# brain-test.net
KiCad netlist of a schematic drawn in EAGLE
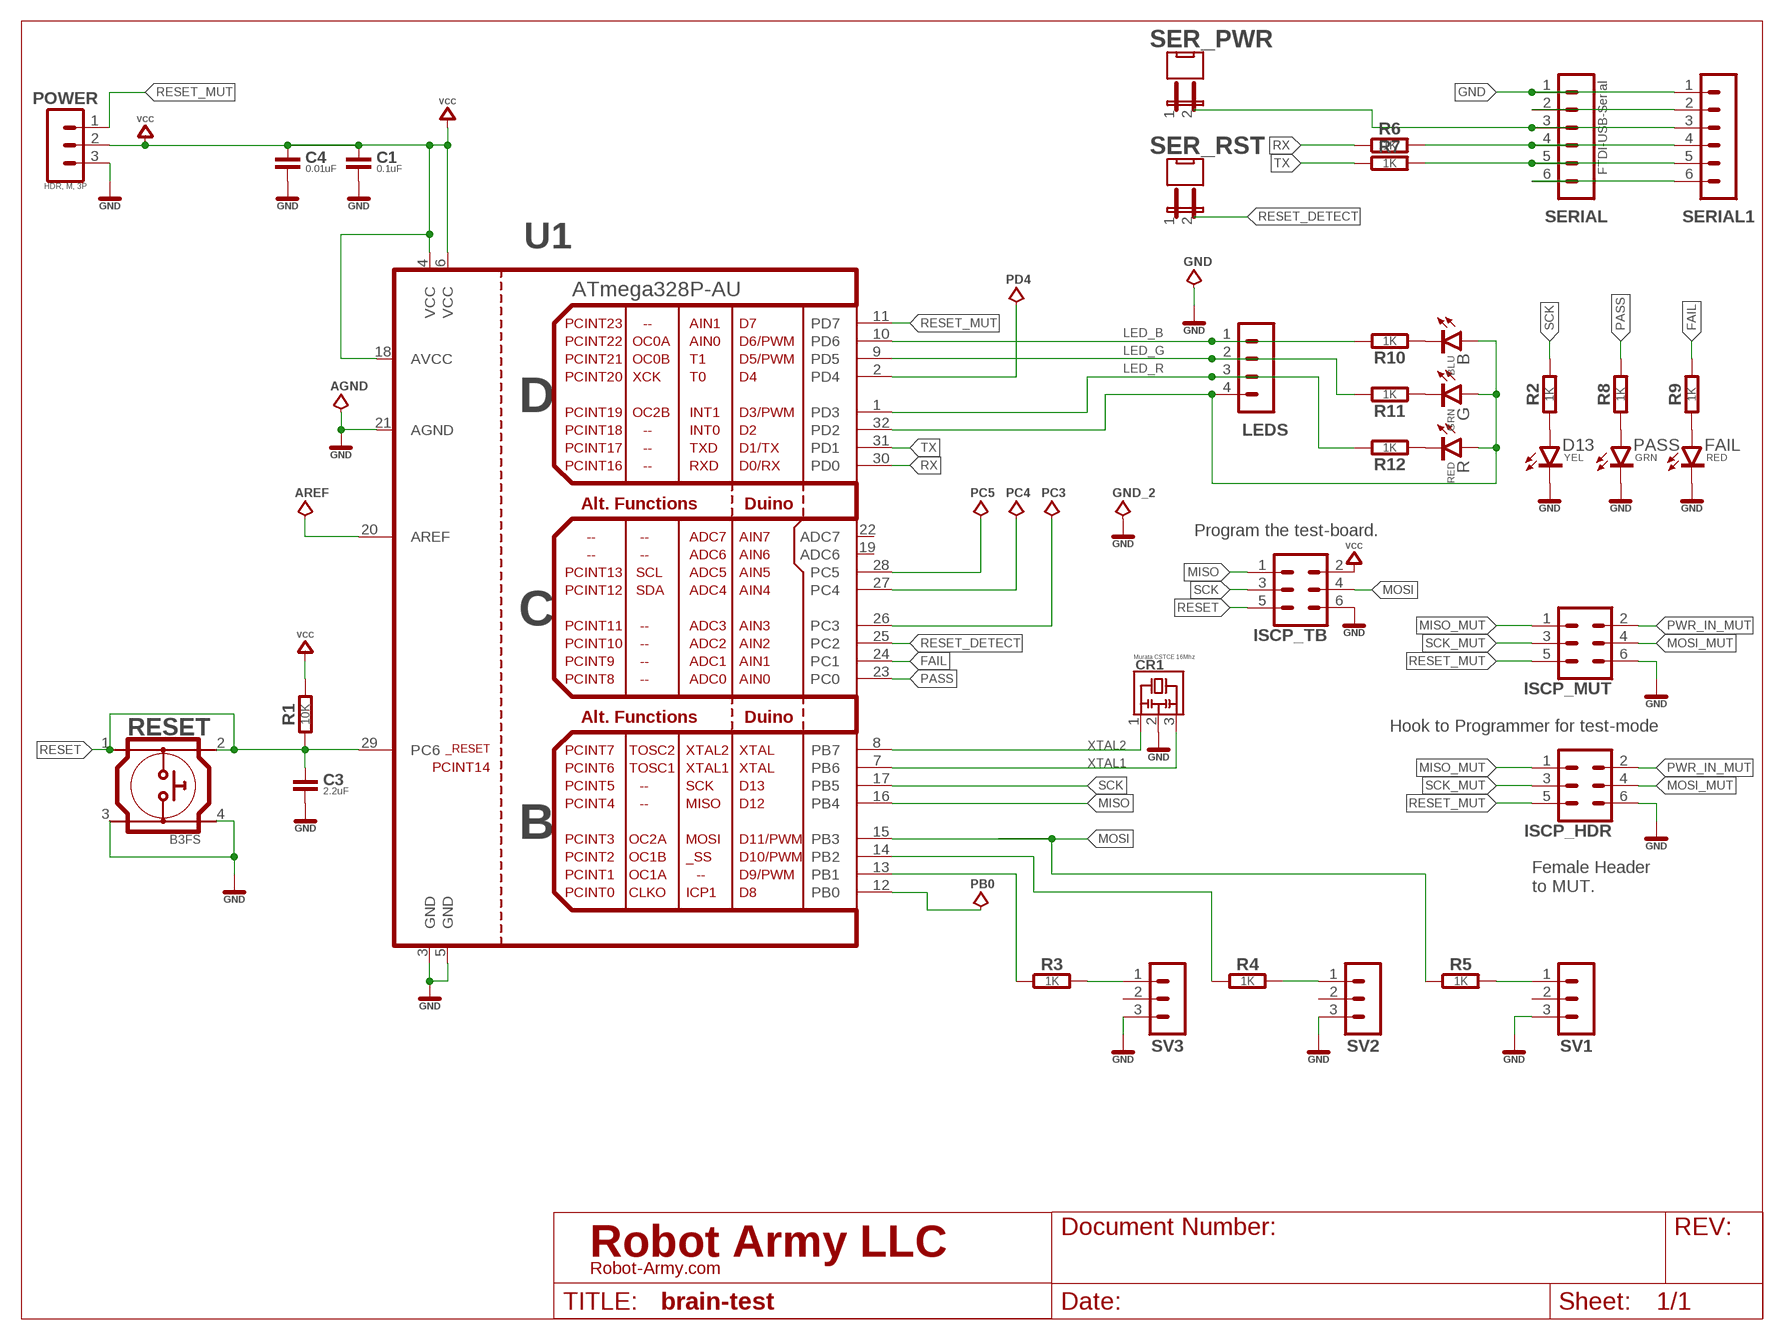
[diagram p0: schematic, sheet 1]

(export (version "E")
  (design (tool "Eeschema 10.0.6"))
  (components
    (comp (ref "AGND")
      (value "TEST_POINT_SM_2X2")
      (footprint "eagle-import:TP-SMT-020X020")
      (libsource (lib "eagle-import") (part "TEST_POINT_SM_2X2"))
    )
    (comp (ref "AREF")
      (value "TEST_POINT_SM_2X2")
      (footprint "eagle-import:TP-SMT-020X020")
      (libsource (lib "eagle-import") (part "TEST_POINT_SM_2X2"))
    )
    (comp (ref "B")
      (value "BLU")
      (footprint "eagle-import:SMD_0603")
      (libsource (lib "eagle-import") (part "SMT0603"))
    )
    (comp (ref "C1")
      (value "0.1uF")
      (footprint "eagle-import:0603")
      (libsource (lib "eagle-import") (part "CAPACITOR0603"))
    )
    (comp (ref "C3")
      (value "2.2uF")
      (footprint "eagle-import:0603")
      (libsource (lib "eagle-import") (part "CAPACITOR0603"))
    )
    (comp (ref "C4")
      (value "0.01uF")
      (footprint "eagle-import:0603")
      (libsource (lib "eagle-import") (part "CAPACITOR0603"))
    )
    (comp (ref "CR1")
      (value "Murata CSTCE 16Mhz")
      (footprint "eagle-import:MURATA_CSTCE")
      (libsource (lib "eagle-import") (part "RESONATORMURATA-CSTCE"))
    )
    (comp (ref "D13")
      (value "YEL")
      (footprint "eagle-import:SMD_0603")
      (libsource (lib "eagle-import") (part "SMT0603"))
    )
    (comp (ref "FAIL")
      (value "RED")
      (footprint "eagle-import:SMD_0603")
      (libsource (lib "eagle-import") (part "SMT0603"))
    )
    (comp (ref "G")
      (value "GRN")
      (footprint "eagle-import:SMD_0603")
      (libsource (lib "eagle-import") (part "SMT0603"))
    )
    (comp (ref "GND")
      (value "TEST_POINT_SM_2X2")
      (footprint "eagle-import:TP-SMT-020X020")
      (libsource (lib "eagle-import") (part "TEST_POINT_SM_2X2"))
    )
    (comp (ref "GND_2")
      (value "TEST_POINT_SM_2X2")
      (footprint "eagle-import:TP-SMT-020X020")
      (libsource (lib "eagle-import") (part "TEST_POINT_SM_2X2"))
    )
    (comp (ref "ISCP_HDR")
      (value "MA03-2")
      (footprint "eagle-import:MA03-2")
      (libsource (lib "eagle-import") (part "MA03-2"))
    )
    (comp (ref "ISCP_MUT")
      (value "MA03-2")
      (footprint "eagle-import:MA03-2")
      (libsource (lib "eagle-import") (part "MA03-2"))
    )
    (comp (ref "ISCP_TB")
      (value "MA03-2")
      (footprint "eagle-import:MA03-2")
      (libsource (lib "eagle-import") (part "MA03-2"))
    )
    (comp (ref "LEDS")
      (value "MA04-1")
      (footprint "eagle-import:MA04-1")
      (libsource (lib "eagle-import") (part "MA04-1"))
    )
    (comp (ref "PASS")
      (value "GRN")
      (footprint "eagle-import:SMD_0603")
      (libsource (lib "eagle-import") (part "SMT0603"))
    )
    (comp (ref "PB0")
      (value "TEST_POINT_SM_2X2")
      (footprint "eagle-import:TP-SMT-020X020")
      (libsource (lib "eagle-import") (part "TEST_POINT_SM_2X2"))
    )
    (comp (ref "PC3")
      (value "TEST_POINT_SM_2X2")
      (footprint "eagle-import:TP-SMT-020X020")
      (libsource (lib "eagle-import") (part "TEST_POINT_SM_2X2"))
    )
    (comp (ref "PC4")
      (value "TEST_POINT_SM_2X2")
      (footprint "eagle-import:TP-SMT-020X020")
      (libsource (lib "eagle-import") (part "TEST_POINT_SM_2X2"))
    )
    (comp (ref "PC5")
      (value "TEST_POINT_SM_2X2")
      (footprint "eagle-import:TP-SMT-020X020")
      (libsource (lib "eagle-import") (part "TEST_POINT_SM_2X2"))
    )
    (comp (ref "PD4")
      (value "TEST_POINT_SM_2X2")
      (footprint "eagle-import:TP-SMT-020X020")
      (libsource (lib "eagle-import") (part "TEST_POINT_SM_2X2"))
    )
    (comp (ref "POWER")
      (value "HDR, M, 3P")
      (footprint "eagle-import:MA03-1")
      (libsource (lib "eagle-import") (part "MA03-1"))
    )
    (comp (ref "R")
      (value "RED")
      (footprint "eagle-import:SMD_0603")
      (libsource (lib "eagle-import") (part "SMT0603"))
    )
    (comp (ref "R1")
      (value "10K")
      (footprint "eagle-import:0603")
      (libsource (lib "eagle-import") (part "RESISTOR0603"))
    )
    (comp (ref "R2")
      (value "1K")
      (footprint "eagle-import:0603")
      (libsource (lib "eagle-import") (part "RESISTOR0603"))
    )
    (comp (ref "R3")
      (value "1K")
      (footprint "eagle-import:0603")
      (libsource (lib "eagle-import") (part "RESISTOR0603"))
    )
    (comp (ref "R4")
      (value "1K")
      (footprint "eagle-import:0603")
      (libsource (lib "eagle-import") (part "RESISTOR0603"))
    )
    (comp (ref "R5")
      (value "1K")
      (footprint "eagle-import:0603")
      (libsource (lib "eagle-import") (part "RESISTOR0603"))
    )
    (comp (ref "R6")
      (value "1K")
      (footprint "eagle-import:0603")
      (libsource (lib "eagle-import") (part "RESISTOR0603"))
    )
    (comp (ref "R7")
      (value "1K")
      (footprint "eagle-import:0603")
      (libsource (lib "eagle-import") (part "RESISTOR0603"))
    )
    (comp (ref "R8")
      (value "1K")
      (footprint "eagle-import:0603")
      (libsource (lib "eagle-import") (part "RESISTOR0603"))
    )
    (comp (ref "R9")
      (value "1K")
      (footprint "eagle-import:0603")
      (libsource (lib "eagle-import") (part "RESISTOR0603"))
    )
    (comp (ref "R10")
      (value "1K")
      (footprint "eagle-import:0603")
      (libsource (lib "eagle-import") (part "RESISTOR0603"))
    )
    (comp (ref "R11")
      (value "1K")
      (footprint "eagle-import:0603")
      (libsource (lib "eagle-import") (part "RESISTOR0603"))
    )
    (comp (ref "R12")
      (value "1K")
      (footprint "eagle-import:0603")
      (libsource (lib "eagle-import") (part "RESISTOR0603"))
    )
    (comp (ref "RESET")
      (value "B3FS")
      (footprint "eagle-import:B3FS")
      (libsource (lib "eagle-import") (part "PUSHBTN-SP-MOM-4PINB3FS"))
    )
    (comp (ref "SERIAL")
      (value "MA06-1")
      (footprint "eagle-import:MA06-1")
      (libsource (lib "eagle-import") (part "MA06-1"))
    )
    (comp (ref "SERIAL1")
      (value "MA06-1")
      (footprint "eagle-import:MA06-1")
      (libsource (lib "eagle-import") (part "MA06-1"))
    )
    (comp (ref "SER_PWR")
      (value "JMP01VT")
      (footprint "eagle-import:MA02-1-FAT")
      (libsource (lib "eagle-import") (part "JMP01VT"))
    )
    (comp (ref "SER_RST")
      (value "JMP01VT")
      (footprint "eagle-import:MA02-1-FAT")
      (libsource (lib "eagle-import") (part "JMP01VT"))
    )
    (comp (ref "SV1")
      (value "MA03-1")
      (footprint "eagle-import:MA03-1")
      (libsource (lib "eagle-import") (part "MA03-1"))
    )
    (comp (ref "SV2")
      (value "MA03-1")
      (footprint "eagle-import:MA03-1")
      (libsource (lib "eagle-import") (part "MA03-1"))
    )
    (comp (ref "SV3")
      (value "MA03-1")
      (footprint "eagle-import:MA03-1")
      (libsource (lib "eagle-import") (part "MA03-1"))
    )
    (comp (ref "U1")
      (value "ATmega328P-AU")
      (footprint "eagle-import:TQFP-32-08")
      (libsource (lib "eagle-import") (part "ATMEGA328"))
    )
  )
  (nets
    (net (code "1") (name "/LED_B") (class "Default")
      (node (ref "LEDS") (pin "1") (pinfunction "1_1") (pintype "passive"))
      (node (ref "R10") (pin "2") (pinfunction "2_2") (pintype "passive"))
      (node (ref "U1") (pin "10") (pinfunction "PD6_10") (pintype "bidirectional"))
    )
    (net (code "2") (name "/LED_G") (class "Default")
      (node (ref "LEDS") (pin "2") (pinfunction "2_2") (pintype "passive"))
      (node (ref "R11") (pin "2") (pinfunction "2_2") (pintype "passive"))
      (node (ref "U1") (pin "9") (pinfunction "PD5_9") (pintype "bidirectional"))
    )
    (net (code "3") (name "/LED_R") (class "Default")
      (node (ref "LEDS") (pin "3") (pinfunction "3_3") (pintype "passive"))
      (node (ref "R12") (pin "2") (pinfunction "2_2") (pintype "passive"))
      (node (ref "U1") (pin "1") (pinfunction "PD3_1") (pintype "bidirectional"))
    )
    (net (code "4") (name "/XTAL1") (class "Default")
      (node (ref "CR1") (pin "3") (pinfunction "3_3") (pintype "bidirectional"))
      (node (ref "U1") (pin "7") (pinfunction "PB6_7") (pintype "bidirectional"))
    )
    (net (code "5") (name "/XTAL2") (class "Default")
      (node (ref "CR1") (pin "1") (pinfunction "1_1") (pintype "bidirectional"))
      (node (ref "U1") (pin "8") (pinfunction "PB7_8") (pintype "bidirectional"))
    )
    (net (code "6") (name "FAIL") (class "Default")
      (node (ref "R9") (pin "2") (pinfunction "2_2") (pintype "passive"))
      (node (ref "U1") (pin "24") (pinfunction "PC1_24") (pintype "bidirectional"))
    )
    (net (code "7") (name "GND") (class "Default")
      (node (ref "AGND") (pin "1") (pinfunction "P$1_1") (pintype "bidirectional"))
      (node (ref "C1") (pin "2") (pinfunction "2_2") (pintype "passive"))
      (node (ref "C3") (pin "2") (pinfunction "2_2") (pintype "passive"))
      (node (ref "C4") (pin "2") (pinfunction "2_2") (pintype "passive"))
      (node (ref "CR1") (pin "2") (pinfunction "2_2") (pintype "bidirectional"))
      (node (ref "D13") (pin "K") (pinfunction "C_K") (pintype "passive"))
      (node (ref "FAIL") (pin "K") (pinfunction "C_K") (pintype "passive"))
      (node (ref "GND") (pin "1") (pinfunction "P$1_1") (pintype "bidirectional"))
      (node (ref "GND_2") (pin "1") (pinfunction "P$1_1") (pintype "bidirectional"))
      (node (ref "ISCP_HDR") (pin "6") (pinfunction "6_6") (pintype "passive"))
      (node (ref "ISCP_MUT") (pin "6") (pinfunction "6_6") (pintype "passive"))
      (node (ref "ISCP_TB") (pin "6") (pinfunction "6_6") (pintype "passive"))
      (node (ref "PASS") (pin "K") (pinfunction "C_K") (pintype "passive"))
      (node (ref "POWER") (pin "3") (pinfunction "3_3") (pintype "passive"))
      (node (ref "RESET") (pin "3") (pinfunction "3_3") (pintype "bidirectional"))
      (node (ref "RESET") (pin "4") (pinfunction "4_4") (pintype "bidirectional"))
      (node (ref "SERIAL") (pin "1") (pinfunction "1_1") (pintype "passive"))
      (node (ref "SERIAL1") (pin "1") (pinfunction "1_1") (pintype "passive"))
      (node (ref "SV1") (pin "3") (pinfunction "3_3") (pintype "passive"))
      (node (ref "SV2") (pin "3") (pinfunction "3_3") (pintype "passive"))
      (node (ref "SV3") (pin "3") (pinfunction "3_3") (pintype "passive"))
      (node (ref "U1") (pin "21") (pinfunction "AGND_21") (pintype "power_in"))
      (node (ref "U1") (pin "3") (pinfunction "GND_3") (pintype "power_in"))
      (node (ref "U1") (pin "5") (pinfunction "GND_5") (pintype "power_in"))
    )
    (net (code "8") (name "MISO") (class "Default")
      (node (ref "ISCP_TB") (pin "1") (pinfunction "1_1") (pintype "passive"))
      (node (ref "U1") (pin "16") (pinfunction "PB4_16") (pintype "bidirectional"))
    )
    (net (code "9") (name "MISO_MUT") (class "Default")
      (node (ref "ISCP_HDR") (pin "1") (pinfunction "1_1") (pintype "passive"))
      (node (ref "ISCP_MUT") (pin "1") (pinfunction "1_1") (pintype "passive"))
    )
    (net (code "10") (name "MOSI") (class "Default")
      (node (ref "ISCP_TB") (pin "4") (pinfunction "4_4") (pintype "passive"))
      (node (ref "R5") (pin "1") (pinfunction "1_1") (pintype "passive"))
      (node (ref "U1") (pin "15") (pinfunction "PB3_15") (pintype "bidirectional"))
    )
    (net (code "11") (name "MOSI_MUT") (class "Default")
      (node (ref "ISCP_HDR") (pin "4") (pinfunction "4_4") (pintype "passive"))
      (node (ref "ISCP_MUT") (pin "4") (pinfunction "4_4") (pintype "passive"))
    )
    (net (code "12") (name "Net-(AREF-P$1)") (class "Default")
      (node (ref "AREF") (pin "1") (pinfunction "P$1_1") (pintype "bidirectional"))
      (node (ref "U1") (pin "20") (pinfunction "AREF_20") (pintype "input"))
    )
    (net (code "13") (name "Net-(B-C)") (class "Default")
      (node (ref "B") (pin "K") (pinfunction "C_K") (pintype "passive"))
      (node (ref "R10") (pin "1") (pinfunction "1_1") (pintype "passive"))
    )
    (net (code "14") (name "Net-(D13-PadA)") (class "Default")
      (node (ref "D13") (pin "A") (pinfunction "A_A") (pintype "passive"))
      (node (ref "R2") (pin "1") (pinfunction "1_1") (pintype "passive"))
    )
    (net (code "15") (name "Net-(FAIL-PadA)") (class "Default")
      (node (ref "FAIL") (pin "A") (pinfunction "A_A") (pintype "passive"))
      (node (ref "R9") (pin "1") (pinfunction "1_1") (pintype "passive"))
    )
    (net (code "16") (name "Net-(G-C)") (class "Default")
      (node (ref "G") (pin "K") (pinfunction "C_K") (pintype "passive"))
      (node (ref "R11") (pin "1") (pinfunction "1_1") (pintype "passive"))
    )
    (net (code "17") (name "Net-(PASS-PadA)") (class "Default")
      (node (ref "PASS") (pin "A") (pinfunction "A_A") (pintype "passive"))
      (node (ref "R8") (pin "1") (pinfunction "1_1") (pintype "passive"))
    )
    (net (code "18") (name "Net-(PB0-P$1)") (class "Default")
      (node (ref "PB0") (pin "1") (pinfunction "P$1_1") (pintype "bidirectional"))
      (node (ref "U1") (pin "12") (pinfunction "PB0_12") (pintype "bidirectional"))
    )
    (net (code "19") (name "Net-(PC3-P$1)") (class "Default")
      (node (ref "PC3") (pin "1") (pinfunction "P$1_1") (pintype "bidirectional"))
      (node (ref "U1") (pin "26") (pinfunction "PC3_26") (pintype "bidirectional"))
    )
    (net (code "20") (name "Net-(PC4-P$1)") (class "Default")
      (node (ref "PC4") (pin "1") (pinfunction "P$1_1") (pintype "bidirectional"))
      (node (ref "U1") (pin "27") (pinfunction "PC4_27") (pintype "bidirectional"))
    )
    (net (code "21") (name "Net-(PC5-P$1)") (class "Default")
      (node (ref "PC5") (pin "1") (pinfunction "P$1_1") (pintype "bidirectional"))
      (node (ref "U1") (pin "28") (pinfunction "PC5_28") (pintype "bidirectional"))
    )
    (net (code "22") (name "Net-(PD4-P$1)") (class "Default")
      (node (ref "PD4") (pin "1") (pinfunction "P$1_1") (pintype "bidirectional"))
      (node (ref "U1") (pin "2") (pinfunction "PD4_2") (pintype "bidirectional"))
    )
    (net (code "23") (name "Net-(R-C)") (class "Default")
      (node (ref "R") (pin "K") (pinfunction "C_K") (pintype "passive"))
      (node (ref "R12") (pin "1") (pinfunction "1_1") (pintype "passive"))
    )
    (net (code "24") (name "Net-(R3-Pad2)") (class "Default")
      (node (ref "R3") (pin "2") (pinfunction "2_2") (pintype "passive"))
      (node (ref "SV3") (pin "1") (pinfunction "1_1") (pintype "passive"))
    )
    (net (code "25") (name "Net-(R4-Pad2)") (class "Default")
      (node (ref "R4") (pin "2") (pinfunction "2_2") (pintype "passive"))
      (node (ref "SV2") (pin "1") (pinfunction "1_1") (pintype "passive"))
    )
    (net (code "26") (name "Net-(R5-Pad2)") (class "Default")
      (node (ref "R5") (pin "2") (pinfunction "2_2") (pintype "passive"))
      (node (ref "SV1") (pin "1") (pinfunction "1_1") (pintype "passive"))
    )
    (net (code "27") (name "Net-(R6-Pad2)") (class "Default")
      (node (ref "R6") (pin "2") (pinfunction "2_2") (pintype "passive"))
      (node (ref "SERIAL") (pin "4") (pinfunction "4_4") (pintype "passive"))
      (node (ref "SERIAL1") (pin "4") (pinfunction "4_4") (pintype "passive"))
    )
    (net (code "28") (name "Net-(R7-Pad2)") (class "Default")
      (node (ref "R7") (pin "2") (pinfunction "2_2") (pintype "passive"))
      (node (ref "SERIAL") (pin "5") (pinfunction "5_5") (pintype "passive"))
      (node (ref "SERIAL1") (pin "5") (pinfunction "5_5") (pintype "passive"))
    )
    (net (code "29") (name "Net-(SERIAL-Pad2)") (class "Default")
      (node (ref "SERIAL") (pin "2") (pinfunction "2_2") (pintype "passive"))
      (node (ref "SERIAL1") (pin "2") (pinfunction "2_2") (pintype "passive"))
    )
    (net (code "30") (name "Net-(SERIAL-Pad6)") (class "Default")
      (node (ref "SERIAL") (pin "6") (pinfunction "6_6") (pintype "passive"))
      (node (ref "SERIAL1") (pin "6") (pinfunction "6_6") (pintype "passive"))
    )
    (net (code "31") (name "Net-(SER_PWR-P$2)") (class "Default")
      (node (ref "SERIAL") (pin "3") (pinfunction "3_3") (pintype "passive"))
      (node (ref "SERIAL1") (pin "3") (pinfunction "3_3") (pintype "passive"))
      (node (ref "SER_PWR") (pin "2") (pinfunction "P$2_2") (pintype "bidirectional"))
    )
    (net (code "32") (name "Net-(U1-PB1)") (class "Default")
      (node (ref "R3") (pin "1") (pinfunction "1_1") (pintype "passive"))
      (node (ref "U1") (pin "13") (pinfunction "PB1_13") (pintype "bidirectional"))
    )
    (net (code "33") (name "Net-(U1-PB2)") (class "Default")
      (node (ref "R4") (pin "1") (pinfunction "1_1") (pintype "passive"))
      (node (ref "U1") (pin "14") (pinfunction "PB2_14") (pintype "bidirectional"))
    )
    (net (code "34") (name "Net-(U1-PD2)") (class "Default")
      (node (ref "B") (pin "A") (pinfunction "A_A") (pintype "passive"))
      (node (ref "G") (pin "A") (pinfunction "A_A") (pintype "passive"))
      (node (ref "LEDS") (pin "4") (pinfunction "4_4") (pintype "passive"))
      (node (ref "R") (pin "A") (pinfunction "A_A") (pintype "passive"))
      (node (ref "U1") (pin "32") (pinfunction "PD2_32") (pintype "bidirectional"))
    )
    (net (code "35") (name "PASS") (class "Default")
      (node (ref "R8") (pin "2") (pinfunction "2_2") (pintype "passive"))
      (node (ref "U1") (pin "23") (pinfunction "PC0_23") (pintype "bidirectional"))
    )
    (net (code "36") (name "PWR_IN_MUT") (class "Default")
      (node (ref "ISCP_HDR") (pin "2") (pinfunction "2_2") (pintype "passive"))
      (node (ref "ISCP_MUT") (pin "2") (pinfunction "2_2") (pintype "passive"))
    )
    (net (code "37") (name "RESET") (class "Default")
      (node (ref "C3") (pin "1") (pinfunction "1_1") (pintype "passive"))
      (node (ref "ISCP_TB") (pin "5") (pinfunction "5_5") (pintype "passive"))
      (node (ref "R1") (pin "1") (pinfunction "1_1") (pintype "passive"))
      (node (ref "RESET") (pin "1") (pinfunction "1_1") (pintype "bidirectional"))
      (node (ref "RESET") (pin "2") (pinfunction "2_2") (pintype "bidirectional"))
      (node (ref "U1") (pin "29") (pinfunction "PC6_29") (pintype "bidirectional"))
    )
    (net (code "38") (name "RESET_DETECT") (class "Default")
      (node (ref "SER_RST") (pin "2") (pinfunction "P$2_2") (pintype "bidirectional"))
      (node (ref "U1") (pin "25") (pinfunction "PC2_25") (pintype "bidirectional"))
    )
    (net (code "39") (name "RESET_MUT") (class "Default")
      (node (ref "ISCP_HDR") (pin "5") (pinfunction "5_5") (pintype "passive"))
      (node (ref "ISCP_MUT") (pin "5") (pinfunction "5_5") (pintype "passive"))
      (node (ref "POWER") (pin "1") (pinfunction "1_1") (pintype "passive"))
      (node (ref "U1") (pin "11") (pinfunction "PD7_11") (pintype "bidirectional"))
    )
    (net (code "40") (name "RX") (class "Default")
      (node (ref "R6") (pin "1") (pinfunction "1_1") (pintype "passive"))
      (node (ref "U1") (pin "30") (pinfunction "PD0_30") (pintype "bidirectional"))
    )
    (net (code "41") (name "SCK") (class "Default")
      (node (ref "ISCP_TB") (pin "3") (pinfunction "3_3") (pintype "passive"))
      (node (ref "R2") (pin "2") (pinfunction "2_2") (pintype "passive"))
      (node (ref "U1") (pin "17") (pinfunction "PB5_17") (pintype "bidirectional"))
    )
    (net (code "42") (name "SCK_MUT") (class "Default")
      (node (ref "ISCP_HDR") (pin "3") (pinfunction "3_3") (pintype "passive"))
      (node (ref "ISCP_MUT") (pin "3") (pinfunction "3_3") (pintype "passive"))
    )
    (net (code "43") (name "TX") (class "Default")
      (node (ref "R7") (pin "1") (pinfunction "1_1") (pintype "passive"))
      (node (ref "U1") (pin "31") (pinfunction "PD1_31") (pintype "bidirectional"))
    )
    (net (code "44") (name "VCC") (class "Default")
      (node (ref "C1") (pin "1") (pinfunction "1_1") (pintype "passive"))
      (node (ref "C4") (pin "1") (pinfunction "1_1") (pintype "passive"))
      (node (ref "ISCP_TB") (pin "2") (pinfunction "2_2") (pintype "passive"))
      (node (ref "POWER") (pin "2") (pinfunction "2_2") (pintype "passive"))
      (node (ref "R1") (pin "2") (pinfunction "2_2") (pintype "passive"))
      (node (ref "U1") (pin "18") (pinfunction "AVCC_18") (pintype "power_in"))
      (node (ref "U1") (pin "4") (pinfunction "VCC_4") (pintype "power_in"))
      (node (ref "U1") (pin "6") (pinfunction "VCC_6") (pintype "power_in"))
    )
    (net (code "45") (name "unconnected-(SER_PWR-P$1-Pad1)") (class "Default")
      (node (ref "SER_PWR") (pin "1") (pinfunction "P$1_1") (pintype "bidirectional"))
    )
    (net (code "46") (name "unconnected-(SER_RST-P$1-Pad1)") (class "Default")
      (node (ref "SER_RST") (pin "1") (pinfunction "P$1_1") (pintype "bidirectional"))
    )
    (net (code "47") (name "unconnected-(SV1-Pad2)") (class "Default")
      (node (ref "SV1") (pin "2") (pinfunction "2_2") (pintype "passive"))
    )
    (net (code "48") (name "unconnected-(SV2-Pad2)") (class "Default")
      (node (ref "SV2") (pin "2") (pinfunction "2_2") (pintype "passive"))
    )
    (net (code "49") (name "unconnected-(SV3-Pad2)") (class "Default")
      (node (ref "SV3") (pin "2") (pinfunction "2_2") (pintype "passive"))
    )
    (net (code "50") (name "unconnected-(U1-ADC6-Pad19)") (class "Default")
      (node (ref "U1") (pin "19") (pinfunction "ADC6_19") (pintype "bidirectional"))
    )
    (net (code "51") (name "unconnected-(U1-ADC7-Pad22)") (class "Default")
      (node (ref "U1") (pin "22") (pinfunction "ADC7_22") (pintype "bidirectional"))
    )
  )
)
